# PSU_only.net
KiCad netlist of a schematic drawn in EAGLE
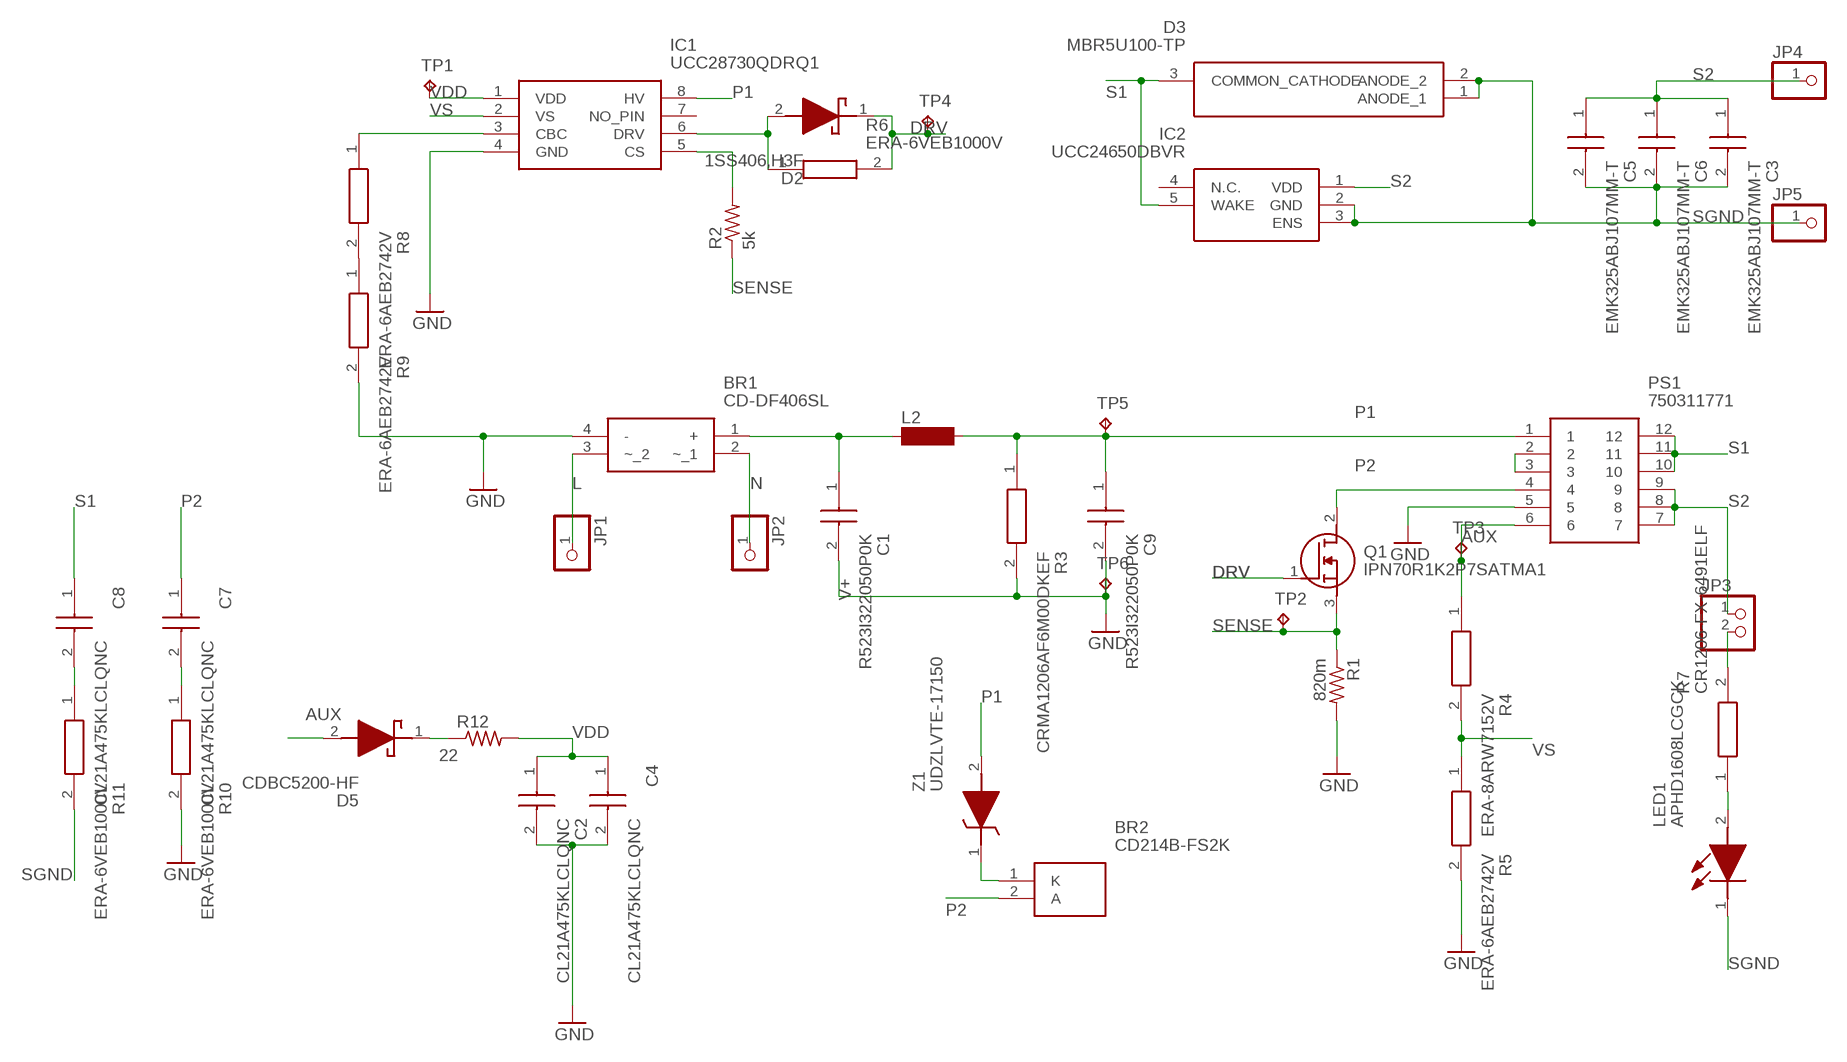
[diagram p0: schematic, sheet 1]

(export (version "E")
  (design (tool "Eeschema 10.0.6"))
  (components
    (comp (ref "BR1")
      (value "CD-DF406SL")
      (footprint "eagle-import:CDDF406SL")
      (fields (field (name "MOUSER_PART_NUMBER") "652-CD-DF406SL"))
      (libsource (lib "eagle-import") (part "CD-DF406SL"))
    )
    (comp (ref "BR2")
      (value "CD214B-FS2K")
      (footprint "eagle-import:CD214BFS2K")
      (fields (field (name "MOUSER_PART_NUMBER") "652-CD214B-FS2K"))
      (libsource (lib "eagle-import") (part "CD214B-FS2K"))
    )
    (comp (ref "C1")
      (value "R523I322050P0K")
      (footprint "eagle-import:HDRV2W65P0X1500_1X2_1790X585X1")
      (libsource (lib "eagle-import") (part "R523I322050P0K"))
    )
    (comp (ref "C2")
      (value "CL21A475KLCLQNC")
      (footprint "eagle-import:CAPC2012X95N")
      (fields (field (name "MOUSER_PART_NUMBER") "187-CL21A475KLCLQNC"))
      (libsource (lib "eagle-import") (part "CL21A475KLCLQNC"))
    )
    (comp (ref "C3")
      (value "EMK325ABJ107MM-T")
      (footprint "eagle-import:CAPC3225X270N")
      (fields (field (name "MOUSER_PART_NUMBER") "963-EMK325ABJ107MM-T"))
      (libsource (lib "eagle-import") (part "EMK325ABJ107MM-T"))
    )
    (comp (ref "C4")
      (value "CL21A475KLCLQNC")
      (footprint "eagle-import:CAPC2012X95N")
      (fields (field (name "MOUSER_PART_NUMBER") "187-CL21A475KLCLQNC"))
      (libsource (lib "eagle-import") (part "CL21A475KLCLQNC"))
    )
    (comp (ref "C5")
      (value "EMK325ABJ107MM-T")
      (footprint "eagle-import:CAPC3225X270N")
      (fields (field (name "MOUSER_PART_NUMBER") "963-EMK325ABJ107MM-T"))
      (libsource (lib "eagle-import") (part "EMK325ABJ107MM-T"))
    )
    (comp (ref "C6")
      (value "EMK325ABJ107MM-T")
      (footprint "eagle-import:CAPC3225X270N")
      (fields (field (name "MOUSER_PART_NUMBER") "963-EMK325ABJ107MM-T"))
      (libsource (lib "eagle-import") (part "EMK325ABJ107MM-T"))
    )
    (comp (ref "C7")
      (value "CL21A475KLCLQNC")
      (footprint "eagle-import:CAPC2012X95N")
      (fields (field (name "MOUSER_PART_NUMBER") "187-CL21A475KLCLQNC"))
      (libsource (lib "eagle-import") (part "CL21A475KLCLQNC"))
    )
    (comp (ref "C8")
      (value "CL21A475KLCLQNC")
      (footprint "eagle-import:CAPC2012X95N")
      (fields (field (name "MOUSER_PART_NUMBER") "187-CL21A475KLCLQNC"))
      (libsource (lib "eagle-import") (part "CL21A475KLCLQNC"))
    )
    (comp (ref "C9")
      (value "R523I322050P0K")
      (footprint "eagle-import:HDRV2W65P0X1500_1X2_1790X585X1")
      (libsource (lib "eagle-import") (part "R523I322050P0K"))
    )
    (comp (ref "D2")
      (value "1SS406,H3F")
      (footprint "eagle-import:SOD2513X115N")
      (fields (field (name "MOUSER_PART_NUMBER") "757-1SS406H3F"))
      (libsource (lib "eagle-import") (part "1SS406,H3F"))
    )
    (comp (ref "D3")
      (value "MBR5U100-TP")
      (footprint "eagle-import:MBR5U100TP")
      (libsource (lib "eagle-import") (part "MBR5U100-TP"))
    )
    (comp (ref "D5")
      (value "CDBC5200-HF")
      (footprint "eagle-import:DIOM8059X290N")
      (fields (field (name "MOUSER_PART_NUMBER") "750-CDBC5200-HF"))
      (libsource (lib "eagle-import") (part "CDBC5200-HF"))
    )
    (comp (ref "IC1")
      (value "UCC28730QDRQ1")
      (footprint "eagle-import:SOIC127P600X175-8N")
      (fields (field (name "MOUSER_PART_NUMBER") "595-UCC28730QDRQ1"))
      (libsource (lib "eagle-import") (part "UCC28730QDRQ1"))
    )
    (comp (ref "IC2")
      (value "UCC24650DBVR")
      (footprint "eagle-import:SOT95P280X145-5N")
      (fields (field (name "MOUSER_PART_NUMBER") "595-UCC24650DBVR"))
      (libsource (lib "eagle-import") (part "UCC24650DBVR"))
    )
    (comp (ref "JP1")
      (value "PINHD-1X1")
      (footprint "eagle-import:1X01")
      (libsource (lib "eagle-import") (part "PINHD-1X1"))
    )
    (comp (ref "JP2")
      (value "PINHD-1X1")
      (footprint "eagle-import:1X01")
      (libsource (lib "eagle-import") (part "PINHD-1X1"))
    )
    (comp (ref "JP3")
      (value "PINHD-1X2")
      (footprint "eagle-import:1X02")
      (libsource (lib "eagle-import") (part "PINHD-1X2"))
    )
    (comp (ref "JP4")
      (value "PINHD-1X1")
      (footprint "eagle-import:1X01")
      (libsource (lib "eagle-import") (part "PINHD-1X1"))
    )
    (comp (ref "JP5")
      (value "PINHD-1X1")
      (footprint "eagle-import:1X01")
      (libsource (lib "eagle-import") (part "PINHD-1X1"))
    )
    (comp (ref "L2")
      (value "MS50SRU1048-471Y")
      (footprint "eagle-import:INDDFN1000X1000X480-2N")
      (libsource (lib "eagle-import") (part "MS50SRU1048-471Y"))
    )
    (comp (ref "LED1")
      (value "APHD1608LCGCK")
      (footprint "eagle-import:LEDM168X80N")
      (fields (field (name "MOUSER_PART_NUMBER") "604-APHD1608LCGCK"))
      (libsource (lib "eagle-import") (part "APHD1608LCGCK"))
    )
    (comp (ref "PS1")
      (value "750311771")
      (footprint "eagle-import:750311771")
      (fields (field (name "MOUSER_PART_NUMBER") "710-750311771") (field (name "SPICEPREFIX") "X"))
      (libsource (lib "eagle-import") (part "750311771"))
    )
    (comp (ref "Q1")
      (value "IPN70R1K2P7SATMA1")
      (footprint "eagle-import:IPN70R1K2P7SATMA1")
      (fields (field (name "MOUSER_PART_NUMBER") "726-IPN70R1K2P7SATM1"))
      (libsource (lib "eagle-import") (part "IPN70R1K2P7SATMA1"))
    )
    (comp (ref "R1")
      (value "820m")
      (footprint "eagle-import:R0805")
      (libsource (lib "eagle-import") (part "R-US_R0805"))
    )
    (comp (ref "R2")
      (value "5k")
      (footprint "eagle-import:R0805")
      (libsource (lib "eagle-import") (part "R-US_R0805"))
    )
    (comp (ref "R3")
      (value "CRMA1206AF6M00DKEF")
      (footprint "eagle-import:RESC3216X74N")
      (libsource (lib "eagle-import") (part "CRMA1206AF6M00DKEF"))
    )
    (comp (ref "R4")
      (value "ERA-8ARW7152V")
      (footprint "eagle-import:ERA8A_(0805)")
      (fields (field (name "MOUSER_PART_NUMBER") "667-ERA-8ARW7152V"))
      (libsource (lib "eagle-import") (part "ERA-8ARW7152V"))
    )
    (comp (ref "R5")
      (value "ERA-6AEB2742V")
      (footprint "eagle-import:ERA6A_(0805)")
      (fields (field (name "MOUSER_PART_NUMBER") "667-ERA-6AEB2742V"))
      (libsource (lib "eagle-import") (part "ERA-6AEB2742V"))
    )
    (comp (ref "R6")
      (value "ERA-6VEB1000V")
      (footprint "eagle-import:ERA6VK")
      (fields (field (name "MOUSER_PART_NUMBER") "667-ERA-6VEB1000V"))
      (libsource (lib "eagle-import") (part "ERA-6VEB1000V"))
    )
    (comp (ref "R7")
      (value "CR1206-FX-6491ELF")
      (footprint "eagle-import:RESC3216X75N")
      (fields (field (name "MOUSER_PART_NUMBER") "652-CR1206FX-6491ELF"))
      (libsource (lib "eagle-import") (part "CR1206-FX-6491ELF"))
    )
    (comp (ref "R8")
      (value "ERA-6AEB2742V")
      (footprint "eagle-import:ERA6A_(0805)")
      (fields (field (name "MOUSER_PART_NUMBER") "667-ERA-6AEB2742V"))
      (libsource (lib "eagle-import") (part "ERA-6AEB2742V"))
    )
    (comp (ref "R9")
      (value "ERA-6AEB2742V")
      (footprint "eagle-import:ERA6A_(0805)")
      (fields (field (name "MOUSER_PART_NUMBER") "667-ERA-6AEB2742V"))
      (libsource (lib "eagle-import") (part "ERA-6AEB2742V"))
    )
    (comp (ref "R10")
      (value "ERA-6VEB1000V")
      (footprint "eagle-import:ERA6VK")
      (fields (field (name "MOUSER_PART_NUMBER") "667-ERA-6VEB1000V"))
      (libsource (lib "eagle-import") (part "ERA-6VEB1000V"))
    )
    (comp (ref "R11")
      (value "ERA-6VEB1000V")
      (footprint "eagle-import:ERA6VK")
      (fields (field (name "MOUSER_PART_NUMBER") "667-ERA-6VEB1000V"))
      (libsource (lib "eagle-import") (part "ERA-6VEB1000V"))
    )
    (comp (ref "R12")
      (value "22")
      (footprint "eagle-import:R0805")
      (libsource (lib "eagle-import") (part "R-US_R0805"))
    )
    (comp (ref "TP1")
      (value "TPB1,27")
      (footprint "eagle-import:B1,27")
      (libsource (lib "eagle-import") (part "TPB1,27"))
    )
    (comp (ref "TP2")
      (value "TPB1,27")
      (footprint "eagle-import:B1,27")
      (libsource (lib "eagle-import") (part "TPB1,27"))
    )
    (comp (ref "TP3")
      (value "TPB1,27")
      (footprint "eagle-import:B1,27")
      (libsource (lib "eagle-import") (part "TPB1,27"))
    )
    (comp (ref "TP4")
      (value "TPB1,27")
      (footprint "eagle-import:B1,27")
      (libsource (lib "eagle-import") (part "TPB1,27"))
    )
    (comp (ref "TP5")
      (value "TPB1,27")
      (footprint "eagle-import:B1,27")
      (libsource (lib "eagle-import") (part "TPB1,27"))
    )
    (comp (ref "TP6")
      (value "TPB1,27")
      (footprint "eagle-import:B1,27")
      (libsource (lib "eagle-import") (part "TPB1,27"))
    )
    (comp (ref "Z1")
      (value "UDZLVTE-17150")
      (footprint "eagle-import:SODFL2512X90N")
      (fields (field (name "MOUSER_PART_NUMBER") "755-UDZLVTE-17150"))
      (libsource (lib "eagle-import") (part "UDZLVTE-17150"))
    )
  )
  (nets
    (net (code "1") (name "AUX") (class "Default")
      (node (ref "D5") (pin "2") (pinfunction "A_2") (pintype "bidirectional"))
      (node (ref "PS1") (pin "6") (pinfunction "6_6") (pintype "bidirectional"))
      (node (ref "R4") (pin "1") (pinfunction "1_1") (pintype "bidirectional"))
      (node (ref "TP3") (pin "TP") (pinfunction "TP_TP") (pintype "input"))
    )
    (net (code "2") (name "DRV") (class "Default")
      (node (ref "D2") (pin "1") (pinfunction "K_1") (pintype "bidirectional"))
      (node (ref "Q1") (pin "1") (pinfunction "G_1") (pintype "bidirectional"))
      (node (ref "R6") (pin "2") (pinfunction "2_2") (pintype "bidirectional"))
      (node (ref "TP4") (pin "TP") (pinfunction "TP_TP") (pintype "input"))
    )
    (net (code "3") (name "GND") (class "Default")
      (node (ref "BR1") (pin "4") (pinfunction "-_4") (pintype "bidirectional"))
      (node (ref "C1") (pin "2") (pinfunction "2_2") (pintype "bidirectional"))
      (node (ref "C2") (pin "2") (pinfunction "2_2") (pintype "bidirectional"))
      (node (ref "C4") (pin "2") (pinfunction "2_2") (pintype "bidirectional"))
      (node (ref "C9") (pin "2") (pinfunction "2_2") (pintype "bidirectional"))
      (node (ref "IC1") (pin "4") (pinfunction "GND_4") (pintype "bidirectional"))
      (node (ref "PS1") (pin "5") (pinfunction "5_5") (pintype "bidirectional"))
      (node (ref "R1") (pin "2") (pinfunction "2_2") (pintype "passive"))
      (node (ref "R10") (pin "2") (pinfunction "2_2") (pintype "bidirectional"))
      (node (ref "R3") (pin "2") (pinfunction "2_2") (pintype "bidirectional"))
      (node (ref "R5") (pin "2") (pinfunction "2_2") (pintype "bidirectional"))
      (node (ref "R9") (pin "2") (pinfunction "2_2") (pintype "bidirectional"))
      (node (ref "TP6") (pin "TP") (pinfunction "TP_TP") (pintype "input"))
    )
    (net (code "4") (name "L") (class "Default")
      (node (ref "BR1") (pin "3") (pinfunction "~{_2}_3") (pintype "bidirectional"))
      (node (ref "JP1") (pin "1") (pinfunction "1_1") (pintype "passive"))
    )
    (net (code "5") (name "N") (class "Default")
      (node (ref "BR1") (pin "2") (pinfunction "~{_1}_2") (pintype "bidirectional"))
      (node (ref "JP2") (pin "1") (pinfunction "1_1") (pintype "passive"))
    )
    (net (code "6") (name "Net-(BR2-K)") (class "Default")
      (node (ref "BR2") (pin "1") (pinfunction "K_1") (pintype "bidirectional"))
      (node (ref "Z1") (pin "1") (pinfunction "K_1") (pintype "bidirectional"))
    )
    (net (code "7") (name "Net-(C7-Pad2)") (class "Default")
      (node (ref "C7") (pin "2") (pinfunction "2_2") (pintype "bidirectional"))
      (node (ref "R10") (pin "1") (pinfunction "1_1") (pintype "bidirectional"))
    )
    (net (code "8") (name "Net-(C8-Pad2)") (class "Default")
      (node (ref "C8") (pin "2") (pinfunction "2_2") (pintype "bidirectional"))
      (node (ref "R11") (pin "1") (pinfunction "1_1") (pintype "bidirectional"))
    )
    (net (code "9") (name "Net-(D2-A)") (class "Default")
      (node (ref "D2") (pin "2") (pinfunction "A_2") (pintype "bidirectional"))
      (node (ref "IC1") (pin "6") (pinfunction "DRV_6") (pintype "bidirectional"))
      (node (ref "R6") (pin "1") (pinfunction "1_1") (pintype "bidirectional"))
    )
    (net (code "10") (name "Net-(D5-K)") (class "Default")
      (node (ref "D5") (pin "1") (pinfunction "K_1") (pintype "bidirectional"))
      (node (ref "R12") (pin "1") (pinfunction "1_1") (pintype "passive"))
    )
    (net (code "11") (name "Net-(IC1-CBC)") (class "Default")
      (node (ref "IC1") (pin "3") (pinfunction "CBC_3") (pintype "bidirectional"))
      (node (ref "R8") (pin "1") (pinfunction "1_1") (pintype "bidirectional"))
    )
    (net (code "12") (name "Net-(IC1-CS)") (class "Default")
      (node (ref "IC1") (pin "5") (pinfunction "CS_5") (pintype "bidirectional"))
      (node (ref "R2") (pin "2") (pinfunction "2_2") (pintype "passive"))
    )
    (net (code "13") (name "Net-(JP3-Pad2)") (class "Default")
      (node (ref "JP3") (pin "2") (pinfunction "2_2") (pintype "passive"))
      (node (ref "R7") (pin "2") (pinfunction "2_2") (pintype "bidirectional"))
    )
    (net (code "14") (name "Net-(LED1-A)") (class "Default")
      (node (ref "LED1") (pin "2") (pinfunction "A_2") (pintype "bidirectional"))
      (node (ref "R7") (pin "1") (pinfunction "1_1") (pintype "bidirectional"))
    )
    (net (code "15") (name "Net-(PS1-Pad2)") (class "Default")
      (node (ref "PS1") (pin "2") (pinfunction "2_2") (pintype "bidirectional"))
      (node (ref "PS1") (pin "3") (pinfunction "3_3") (pintype "bidirectional"))
    )
    (net (code "16") (name "Net-(R8-Pad2)") (class "Default")
      (node (ref "R8") (pin "2") (pinfunction "2_2") (pintype "bidirectional"))
      (node (ref "R9") (pin "1") (pinfunction "1_1") (pintype "bidirectional"))
    )
    (net (code "17") (name "P1") (class "Default")
      (node (ref "C9") (pin "1") (pinfunction "1_1") (pintype "bidirectional"))
      (node (ref "IC1") (pin "8") (pinfunction "HV_8") (pintype "bidirectional"))
      (node (ref "L2") (pin "2") (pinfunction "2_2") (pintype "passive"))
      (node (ref "PS1") (pin "1") (pinfunction "1_1") (pintype "bidirectional"))
      (node (ref "R3") (pin "1") (pinfunction "1_1") (pintype "bidirectional"))
      (node (ref "TP5") (pin "TP") (pinfunction "TP_TP") (pintype "input"))
      (node (ref "Z1") (pin "2") (pinfunction "A_2") (pintype "bidirectional"))
    )
    (net (code "18") (name "P2") (class "Default")
      (node (ref "BR2") (pin "2") (pinfunction "A_2") (pintype "bidirectional"))
      (node (ref "C7") (pin "1") (pinfunction "1_1") (pintype "bidirectional"))
      (node (ref "PS1") (pin "4") (pinfunction "4_4") (pintype "bidirectional"))
      (node (ref "Q1") (pin "2") (pinfunction "D_2") (pintype "bidirectional"))
    )
    (net (code "19") (name "S1") (class "Default")
      (node (ref "C8") (pin "1") (pinfunction "1_1") (pintype "bidirectional"))
      (node (ref "D3") (pin "3") (pinfunction "COMMON_CATHODE_3") (pintype "bidirectional"))
      (node (ref "IC2") (pin "5") (pinfunction "WAKE_5") (pintype "bidirectional"))
      (node (ref "PS1") (pin "10") (pinfunction "10_10") (pintype "bidirectional"))
      (node (ref "PS1") (pin "11") (pinfunction "11_11") (pintype "bidirectional"))
      (node (ref "PS1") (pin "12") (pinfunction "12_12") (pintype "bidirectional"))
    )
    (net (code "20") (name "S2") (class "Default")
      (node (ref "C3") (pin "1") (pinfunction "1_1") (pintype "bidirectional"))
      (node (ref "C5") (pin "1") (pinfunction "1_1") (pintype "bidirectional"))
      (node (ref "C6") (pin "1") (pinfunction "1_1") (pintype "bidirectional"))
      (node (ref "IC2") (pin "1") (pinfunction "VDD_1") (pintype "bidirectional"))
      (node (ref "JP3") (pin "1") (pinfunction "1_1") (pintype "passive"))
      (node (ref "JP4") (pin "1") (pinfunction "1_1") (pintype "passive"))
      (node (ref "PS1") (pin "7") (pinfunction "7_7") (pintype "bidirectional"))
      (node (ref "PS1") (pin "8") (pinfunction "8_8") (pintype "bidirectional"))
      (node (ref "PS1") (pin "9") (pinfunction "9_9") (pintype "bidirectional"))
    )
    (net (code "21") (name "SENSE") (class "Default")
      (node (ref "Q1") (pin "3") (pinfunction "S_3") (pintype "bidirectional"))
      (node (ref "R1") (pin "1") (pinfunction "1_1") (pintype "passive"))
      (node (ref "R2") (pin "1") (pinfunction "1_1") (pintype "passive"))
      (node (ref "TP2") (pin "TP") (pinfunction "TP_TP") (pintype "input"))
    )
    (net (code "22") (name "SGND") (class "Default")
      (node (ref "C3") (pin "2") (pinfunction "2_2") (pintype "bidirectional"))
      (node (ref "C5") (pin "2") (pinfunction "2_2") (pintype "bidirectional"))
      (node (ref "C6") (pin "2") (pinfunction "2_2") (pintype "bidirectional"))
      (node (ref "D3") (pin "1") (pinfunction "ANODE_1_1") (pintype "bidirectional"))
      (node (ref "D3") (pin "2") (pinfunction "ANODE_2_2") (pintype "bidirectional"))
      (node (ref "IC2") (pin "2") (pinfunction "GND_2") (pintype "bidirectional"))
      (node (ref "IC2") (pin "3") (pinfunction "ENS_3") (pintype "bidirectional"))
      (node (ref "JP5") (pin "1") (pinfunction "1_1") (pintype "passive"))
      (node (ref "LED1") (pin "1") (pinfunction "K_1") (pintype "bidirectional"))
      (node (ref "R11") (pin "2") (pinfunction "2_2") (pintype "bidirectional"))
    )
    (net (code "23") (name "V+") (class "Default")
      (node (ref "BR1") (pin "1") (pinfunction "+_1") (pintype "bidirectional"))
      (node (ref "C1") (pin "1") (pinfunction "1_1") (pintype "bidirectional"))
      (node (ref "L2") (pin "1") (pinfunction "1_1") (pintype "passive"))
    )
    (net (code "24") (name "VDD") (class "Default")
      (node (ref "C2") (pin "1") (pinfunction "1_1") (pintype "bidirectional"))
      (node (ref "C4") (pin "1") (pinfunction "1_1") (pintype "bidirectional"))
      (node (ref "IC1") (pin "1") (pinfunction "VDD_1") (pintype "bidirectional"))
      (node (ref "R12") (pin "2") (pinfunction "2_2") (pintype "passive"))
      (node (ref "TP1") (pin "TP") (pinfunction "TP_TP") (pintype "input"))
    )
    (net (code "25") (name "VS") (class "Default")
      (node (ref "IC1") (pin "2") (pinfunction "VS_2") (pintype "bidirectional"))
      (node (ref "R4") (pin "2") (pinfunction "2_2") (pintype "bidirectional"))
      (node (ref "R5") (pin "1") (pinfunction "1_1") (pintype "bidirectional"))
    )
    (net (code "26") (name "unconnected-(IC1-NO_PIN-Pad7)") (class "Default")
      (node (ref "IC1") (pin "7") (pinfunction "NO_PIN_7") (pintype "bidirectional"))
    )
    (net (code "27") (name "unconnected-(IC2-N.C.-Pad4)") (class "Default")
      (node (ref "IC2") (pin "4") (pinfunction "N.C._4") (pintype "no_connect"))
    )
  )
)
